# SDDD.net
KiCad netlist of a schematic drawn in Altium Designer
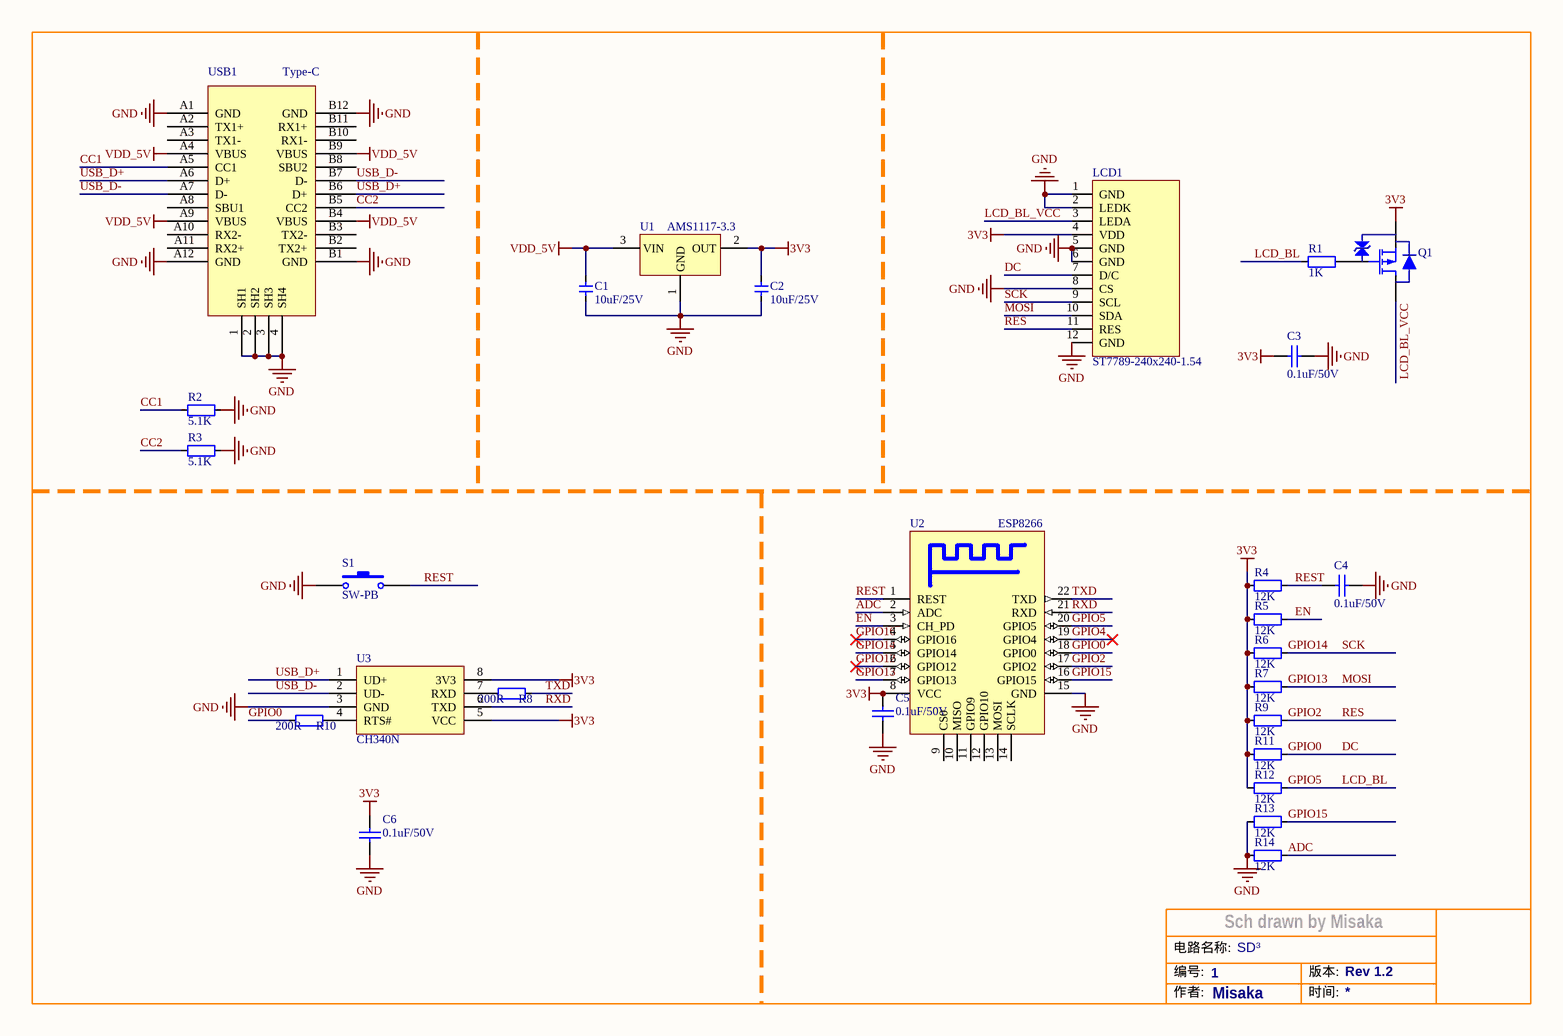
[diagram p0: SDDD.SchDoc]

(export (version "E")
  (design (tool "Eeschema 10.0.6"))
  (components
    (comp (ref "C1")
      (value "10uF/25V")
      (footprint "C_0603")
      (description "Capacitor")
      (libsource (lib "MyPcbLib") (part "电容-0402"))
    )
    (comp (ref "C2")
      (value "10uF/25V")
      (footprint "C_0603")
      (description "Capacitor")
      (libsource (lib "MyPcbLib") (part "电容-0402"))
    )
    (comp (ref "C3")
      (value "0.1uF/50V")
      (footprint "C_0603")
      (description "Capacitor")
      (fields (field (name "PUBLISHER") "Altium Limited"))
      (libsource (lib "Miscellaneous Devices") (part "Cap"))
    )
    (comp (ref "C4")
      (value "0.1uF/50V")
      (footprint "C_0603")
      (description "Capacitor")
      (fields (field (name "PUBLISHER") "Altium Limited"))
      (libsource (lib "Miscellaneous Devices") (part "Cap"))
    )
    (comp (ref "C5")
      (value "0.1uF/50V")
      (footprint "C_0603")
      (description "Capacitor")
      (fields (field (name "PUBLISHER") "Altium Limited"))
      (libsource (lib "Miscellaneous Devices") (part "Cap"))
    )
    (comp (ref "C6")
      (value "0.1uF/50V")
      (footprint "C_0603")
      (description "Capacitor")
      (fields (field (name "PUBLISHER") "Altium Limited"))
      (libsource (lib "Miscellaneous Devices") (part "Cap"))
    )
    (comp (ref "LCD1")
      (value "ST7789-240x240-1.54")
      (footprint "LCD-240X240-12P")
      (description "显示屏")
      (libsource (lib "mLib") (part "LCD-240x240"))
    )
    (comp (ref "Q1")
      (value "AO3401")
      (footprint "SOT-23-y")
      (description "MOSFET")
      (fields (field (name "PUBLISHER") "Altium Limited"))
      (libsource (lib "MyPcbLib") (part "AO3415A"))
    )
    (comp (ref "R1")
      (value "1K")
      (footprint "R_0603")
      (description "Resistor")
      (libsource (lib "") (part "电阻-0402_2"))
    )
    (comp (ref "R2")
      (value "5.1K")
      (footprint "R_0603")
      (description "Resistor")
      (libsource (lib "MyPcbLib") (part "电阻-0402"))
    )
    (comp (ref "R3")
      (value "5.1K")
      (footprint "R_0603")
      (description "Resistor")
      (libsource (lib "MyPcbLib") (part "电阻-0402"))
    )
    (comp (ref "R4")
      (value "12K")
      (footprint "R_0603")
      (description "Resistor")
      (libsource (lib "MyPcbLib") (part "电阻-0402"))
    )
    (comp (ref "R5")
      (value "12K")
      (footprint "R_0603")
      (description "Resistor")
      (libsource (lib "MyPcbLib") (part "电阻-0402"))
    )
    (comp (ref "R6")
      (value "12K")
      (footprint "R_0603")
      (description "Resistor")
      (libsource (lib "MyPcbLib") (part "电阻-0402"))
    )
    (comp (ref "R7")
      (value "12K")
      (footprint "R_0603")
      (description "Resistor")
      (libsource (lib "MyPcbLib") (part "电阻-0402"))
    )
    (comp (ref "R8")
      (value "200R")
      (footprint "R_0603")
      (description "Resistor")
      (libsource (lib "") (part "电阻-0402_1"))
    )
    (comp (ref "R9")
      (value "12K")
      (footprint "R_0603")
      (description "Resistor")
      (libsource (lib "MyPcbLib") (part "电阻-0402"))
    )
    (comp (ref "R10")
      (value "200R")
      (footprint "R_0603")
      (description "Resistor")
      (libsource (lib "") (part "电阻-0402_1"))
    )
    (comp (ref "R11")
      (value "12K")
      (footprint "R_0603")
      (description "Resistor")
      (libsource (lib "MyPcbLib") (part "电阻-0402"))
    )
    (comp (ref "R12")
      (value "12K")
      (footprint "R_0603")
      (description "Resistor")
      (libsource (lib "MyPcbLib") (part "电阻-0402"))
    )
    (comp (ref "R13")
      (value "12K")
      (footprint "R_0603")
      (description "Resistor")
      (libsource (lib "MyPcbLib") (part "电阻-0402"))
    )
    (comp (ref "R14")
      (value "12K")
      (footprint "R_0603")
      (description "Resistor")
      (libsource (lib "MyPcbLib") (part "电阻-0402"))
    )
    (comp (ref "S1")
      (value "SW-PB")
      (footprint "YD-3410")
      (description "小龟")
      (fields (field (name "PUBLISHER") "Altium Limited"))
      (libsource (lib "Miscellaneous Devices") (part "SW-PB"))
    )
    (comp (ref "U1") (value "AMS1117-3.3") (footprint "SOT223_y") (libsource (lib "数控电源") (part "LM317M")))
    (comp (ref "U2")
      (value "ESP8266")
      (footprint "8266")
      (description "ESP-12F")
      (libsource (lib "Misaka") (part "ESP8266"))
    )
    (comp (ref "U3") (value "CH340N") (footprint "SO-8") (libsource (lib "Misaka") (part "CH340N")))
    (comp (ref "USB1")
      (value "Type-C")
      (footprint "Misaka:Type-C-TOP")
      (libsource (lib "MyPcbLib") (part "USB-Type-C-TOP"))
    )
  )
  (nets
    (net (code "1") (name "/ADC") (class "Default")
      (node (ref "R14") (pin "2") (pinfunction "2_2") (pintype "passive"))
      (node (ref "U2") (pin "2") (pinfunction "ADC_2") (pintype "input"))
    )
    (net (code "2") (name "/CC1") (class "Default")
      (node (ref "R2") (pin "1") (pinfunction "1_1") (pintype "passive"))
      (node (ref "USB1") (pin "A5") (pinfunction "CC1_A5") (pintype "passive"))
    )
    (net (code "3") (name "/CC2") (class "Default")
      (node (ref "R3") (pin "1") (pinfunction "1_1") (pintype "passive"))
      (node (ref "USB1") (pin "B5") (pinfunction "CC2_B5") (pintype "passive"))
    )
    (net (code "4") (name "/DC") (class "Default")
      (node (ref "LCD1") (pin "7") (pinfunction "D/C_7") (pintype "passive"))
      (node (ref "R10") (pin "2") (pinfunction "2_2") (pintype "passive"))
      (node (ref "R11") (pin "2") (pinfunction "2_2") (pintype "passive"))
      (node (ref "U2") (pin "18") (pinfunction "GPIO0_18") (pintype "bidirectional"))
    )
    (net (code "5") (name "/EN") (class "Default")
      (node (ref "R5") (pin "2") (pinfunction "2_2") (pintype "passive"))
      (node (ref "U2") (pin "3") (pinfunction "CH_PD_3") (pintype "input"))
    )
    (net (code "6") (name "/GPIO2") (class "Default")
      (node (ref "LCD1") (pin "11") (pinfunction "RES_11") (pintype "passive"))
      (node (ref "R9") (pin "2") (pinfunction "2_2") (pintype "passive"))
      (node (ref "U2") (pin "17") (pinfunction "GPIO2_17") (pintype "bidirectional"))
    )
    (net (code "7") (name "/GPIO4") (class "Default")
      (node (ref "U2") (pin "19") (pinfunction "GPIO4_19") (pintype "bidirectional+no_connect"))
    )
    (net (code "8") (name "/GPIO5") (class "Default")
      (node (ref "R1") (pin "1") (pinfunction "1_1") (pintype "passive"))
      (node (ref "R12") (pin "2") (pinfunction "2_2") (pintype "passive"))
      (node (ref "U2") (pin "20") (pinfunction "GPIO5_20") (pintype "bidirectional"))
    )
    (net (code "9") (name "/GPIO12") (class "Default")
      (node (ref "U2") (pin "6") (pinfunction "GPIO12_6") (pintype "bidirectional+no_connect"))
    )
    (net (code "10") (name "/GPIO13") (class "Default")
      (node (ref "LCD1") (pin "10") (pinfunction "SDA_10") (pintype "passive"))
      (node (ref "R7") (pin "2") (pinfunction "2_2") (pintype "passive"))
      (node (ref "U2") (pin "7") (pinfunction "GPIO13_7") (pintype "bidirectional"))
    )
    (net (code "11") (name "/GPIO14") (class "Default")
      (node (ref "LCD1") (pin "9") (pinfunction "SCL_9") (pintype "passive"))
      (node (ref "R6") (pin "2") (pinfunction "2_2") (pintype "passive"))
      (node (ref "U2") (pin "5") (pinfunction "GPIO14_5") (pintype "bidirectional"))
    )
    (net (code "12") (name "/GPIO15") (class "Default")
      (node (ref "R13") (pin "2") (pinfunction "2_2") (pintype "passive"))
      (node (ref "U2") (pin "16") (pinfunction "GPIO15_16") (pintype "bidirectional"))
    )
    (net (code "13") (name "/GPIO16") (class "Default")
      (node (ref "U2") (pin "4") (pinfunction "GPIO16_4") (pintype "bidirectional+no_connect"))
    )
    (net (code "14") (name "/LCD_BL_VCC") (class "Default")
      (node (ref "LCD1") (pin "3") (pinfunction "LEDA_3") (pintype "passive"))
      (node (ref "Q1") (pin "3") (pinfunction "D_3") (pintype "passive"))
    )
    (net (code "15") (name "/REST") (class "Default")
      (node (ref "C4") (pin "2") (pinfunction "2_2") (pintype "passive"))
      (node (ref "R4") (pin "2") (pinfunction "2_2") (pintype "passive"))
      (node (ref "S1") (pin "2") (pinfunction "2_2") (pintype "passive"))
      (node (ref "U2") (pin "1") (pinfunction "REST_1") (pintype "passive"))
    )
    (net (code "16") (name "/RXD") (class "Default")
      (node (ref "U2") (pin "21") (pinfunction "RXD_21") (pintype "input"))
      (node (ref "U3") (pin "6") (pinfunction "TXD_6") (pintype "passive"))
    )
    (net (code "17") (name "/TXD") (class "Default")
      (node (ref "R8") (pin "1") (pinfunction "1_1") (pintype "passive"))
      (node (ref "U2") (pin "22") (pinfunction "TXD_22") (pintype "output"))
    )
    (net (code "18") (name "/USB_D+") (class "Default")
      (node (ref "U3") (pin "1") (pinfunction "UD+_1") (pintype "passive"))
      (node (ref "USB1") (pin "A6") (pinfunction "D+_A6") (pintype "passive"))
      (node (ref "USB1") (pin "B6") (pinfunction "D+_B6") (pintype "passive"))
    )
    (net (code "19") (name "/USB_D-") (class "Default")
      (node (ref "U3") (pin "2") (pinfunction "UD-_2") (pintype "passive"))
      (node (ref "USB1") (pin "A7") (pinfunction "D-_A7") (pintype "passive"))
      (node (ref "USB1") (pin "B7") (pinfunction "D-_B7") (pintype "passive"))
    )
    (net (code "20") (name "3V3") (class "Default")
      (node (ref "C2") (pin "2") (pinfunction "2_2") (pintype "passive"))
      (node (ref "C3") (pin "2") (pinfunction "2_2") (pintype "passive"))
      (node (ref "C5") (pin "2") (pinfunction "2_2") (pintype "passive"))
      (node (ref "C6") (pin "2") (pinfunction "2_2") (pintype "passive"))
      (node (ref "LCD1") (pin "4") (pinfunction "VDD_4") (pintype "passive"))
      (node (ref "Q1") (pin "2") (pinfunction "S_2") (pintype "passive"))
      (node (ref "R11") (pin "1") (pinfunction "1_1") (pintype "passive"))
      (node (ref "R12") (pin "1") (pinfunction "1_1") (pintype "passive"))
      (node (ref "R4") (pin "1") (pinfunction "1_1") (pintype "passive"))
      (node (ref "R5") (pin "1") (pinfunction "1_1") (pintype "passive"))
      (node (ref "R6") (pin "1") (pinfunction "1_1") (pintype "passive"))
      (node (ref "R7") (pin "1") (pinfunction "1_1") (pintype "passive"))
      (node (ref "R9") (pin "1") (pinfunction "1_1") (pintype "passive"))
      (node (ref "U1") (pin "2") (pinfunction "OUT_2") (pintype "passive"))
      (node (ref "U2") (pin "8") (pinfunction "VCC_8") (pintype "power_in"))
      (node (ref "U3") (pin "5") (pinfunction "VCC_5") (pintype "passive"))
      (node (ref "U3") (pin "8") (pinfunction "3V3_8") (pintype "passive"))
    )
    (net (code "21") (name "GND") (class "Default")
      (node (ref "C1") (pin "1") (pinfunction "1_1") (pintype "passive"))
      (node (ref "C2") (pin "1") (pinfunction "1_1") (pintype "passive"))
      (node (ref "C3") (pin "1") (pinfunction "1_1") (pintype "passive"))
      (node (ref "C4") (pin "1") (pinfunction "1_1") (pintype "passive"))
      (node (ref "C5") (pin "1") (pinfunction "1_1") (pintype "passive"))
      (node (ref "C6") (pin "1") (pinfunction "1_1") (pintype "passive"))
      (node (ref "LCD1") (pin "1") (pinfunction "GND_1") (pintype "passive"))
      (node (ref "LCD1") (pin "12") (pinfunction "GND_12") (pintype "passive"))
      (node (ref "LCD1") (pin "2") (pinfunction "LEDK_2") (pintype "passive"))
      (node (ref "LCD1") (pin "5") (pinfunction "GND_5") (pintype "passive"))
      (node (ref "LCD1") (pin "6") (pinfunction "GND_6") (pintype "passive"))
      (node (ref "LCD1") (pin "8") (pinfunction "CS_8") (pintype "passive"))
      (node (ref "R13") (pin "1") (pinfunction "1_1") (pintype "passive"))
      (node (ref "R14") (pin "1") (pinfunction "1_1") (pintype "passive"))
      (node (ref "R2") (pin "2") (pinfunction "2_2") (pintype "passive"))
      (node (ref "R3") (pin "2") (pinfunction "2_2") (pintype "passive"))
      (node (ref "S1") (pin "1") (pinfunction "1_1") (pintype "passive"))
      (node (ref "U1") (pin "1") (pinfunction "GND_1") (pintype "passive"))
      (node (ref "U2") (pin "15") (pinfunction "GND_15") (pintype "power_in"))
      (node (ref "U3") (pin "3") (pinfunction "GND_3") (pintype "passive"))
      (node (ref "USB1") (pin "1") (pinfunction "SH1_1") (pintype "passive"))
      (node (ref "USB1") (pin "2") (pinfunction "SH2_2") (pintype "passive"))
      (node (ref "USB1") (pin "3") (pinfunction "SH3_3") (pintype "passive"))
      (node (ref "USB1") (pin "4") (pinfunction "SH4_4") (pintype "passive"))
      (node (ref "USB1") (pin "A1") (pinfunction "GND_A1") (pintype "passive"))
      (node (ref "USB1") (pin "A12") (pinfunction "GND_A12") (pintype "passive"))
      (node (ref "USB1") (pin "B1") (pinfunction "GND_B1") (pintype "passive"))
      (node (ref "USB1") (pin "B12") (pinfunction "GND_B12") (pintype "passive"))
    )
    (net (code "22") (name "Net-(Q1-G)") (class "Default")
      (node (ref "Q1") (pin "1") (pinfunction "G_1") (pintype "passive"))
      (node (ref "R1") (pin "2") (pinfunction "2_2") (pintype "passive"))
    )
    (net (code "23") (name "Net-(U3-RTS#)") (class "Default")
      (node (ref "R10") (pin "1") (pinfunction "1_1") (pintype "passive"))
      (node (ref "U3") (pin "4") (pinfunction "RTS#_4") (pintype "passive"))
    )
    (net (code "24") (name "Net-(U3-RXD)") (class "Default")
      (node (ref "R8") (pin "2") (pinfunction "2_2") (pintype "passive"))
      (node (ref "U3") (pin "7") (pinfunction "RXD_7") (pintype "passive"))
    )
    (net (code "25") (name "VDD_5V") (class "Default")
      (node (ref "C1") (pin "2") (pinfunction "2_2") (pintype "passive"))
      (node (ref "U1") (pin "3") (pinfunction "VIN_3") (pintype "passive"))
      (node (ref "USB1") (pin "A4") (pinfunction "VBUS_A4") (pintype "passive"))
      (node (ref "USB1") (pin "A9") (pinfunction "VBUS_A9") (pintype "passive"))
      (node (ref "USB1") (pin "B4") (pinfunction "VBUS_B4") (pintype "passive"))
      (node (ref "USB1") (pin "B9") (pinfunction "VBUS_B9") (pintype "passive"))
    )
    (net (code "26") (name "unconnected-(U2-CS0-Pad9)") (class "Default")
      (node (ref "U2") (pin "9") (pinfunction "CS0_9") (pintype "passive"))
    )
    (net (code "27") (name "unconnected-(U2-GPIO9-Pad11)") (class "Default")
      (node (ref "U2") (pin "11") (pinfunction "GPIO9_11") (pintype "passive"))
    )
    (net (code "28") (name "unconnected-(U2-GPIO10-Pad12)") (class "Default")
      (node (ref "U2") (pin "12") (pinfunction "GPIO10_12") (pintype "passive"))
    )
    (net (code "29") (name "unconnected-(U2-MISO-Pad10)") (class "Default")
      (node (ref "U2") (pin "10") (pinfunction "MISO_10") (pintype "passive"))
    )
    (net (code "30") (name "unconnected-(U2-MOSI-Pad13)") (class "Default")
      (node (ref "U2") (pin "13") (pinfunction "MOSI_13") (pintype "passive"))
    )
    (net (code "31") (name "unconnected-(U2-SCLK-Pad14)") (class "Default")
      (node (ref "U2") (pin "14") (pinfunction "SCLK_14") (pintype "passive"))
    )
    (net (code "32") (name "unconnected-(USB1-RX1+-PadB11)") (class "Default")
      (node (ref "USB1") (pin "B11") (pinfunction "RX1+_B11") (pintype "passive"))
    )
    (net (code "33") (name "unconnected-(USB1-RX1--PadB10)") (class "Default")
      (node (ref "USB1") (pin "B10") (pinfunction "RX1-_B10") (pintype "passive"))
    )
    (net (code "34") (name "unconnected-(USB1-RX2+-PadA11)") (class "Default")
      (node (ref "USB1") (pin "A11") (pinfunction "RX2+_A11") (pintype "passive"))
    )
    (net (code "35") (name "unconnected-(USB1-RX2--PadA10)") (class "Default")
      (node (ref "USB1") (pin "A10") (pinfunction "RX2-_A10") (pintype "passive"))
    )
    (net (code "36") (name "unconnected-(USB1-SBU1-PadA8)") (class "Default")
      (node (ref "USB1") (pin "A8") (pinfunction "SBU1_A8") (pintype "passive"))
    )
    (net (code "37") (name "unconnected-(USB1-SBU2-PadB8)") (class "Default")
      (node (ref "USB1") (pin "B8") (pinfunction "SBU2_B8") (pintype "passive"))
    )
    (net (code "38") (name "unconnected-(USB1-TX1+-PadA2)") (class "Default")
      (node (ref "USB1") (pin "A2") (pinfunction "TX1+_A2") (pintype "passive"))
    )
    (net (code "39") (name "unconnected-(USB1-TX1--PadA3)") (class "Default")
      (node (ref "USB1") (pin "A3") (pinfunction "TX1-_A3") (pintype "passive"))
    )
    (net (code "40") (name "unconnected-(USB1-TX2+-PadB2)") (class "Default")
      (node (ref "USB1") (pin "B2") (pinfunction "TX2+_B2") (pintype "passive"))
    )
    (net (code "41") (name "unconnected-(USB1-TX2--PadB3)") (class "Default")
      (node (ref "USB1") (pin "B3") (pinfunction "TX2-_B3") (pintype "passive"))
    )
  )
)
